# Adafruit_I2C_Quad_Rotary_Encoder_Breakou.net
KiCad netlist of a schematic drawn in EAGLE
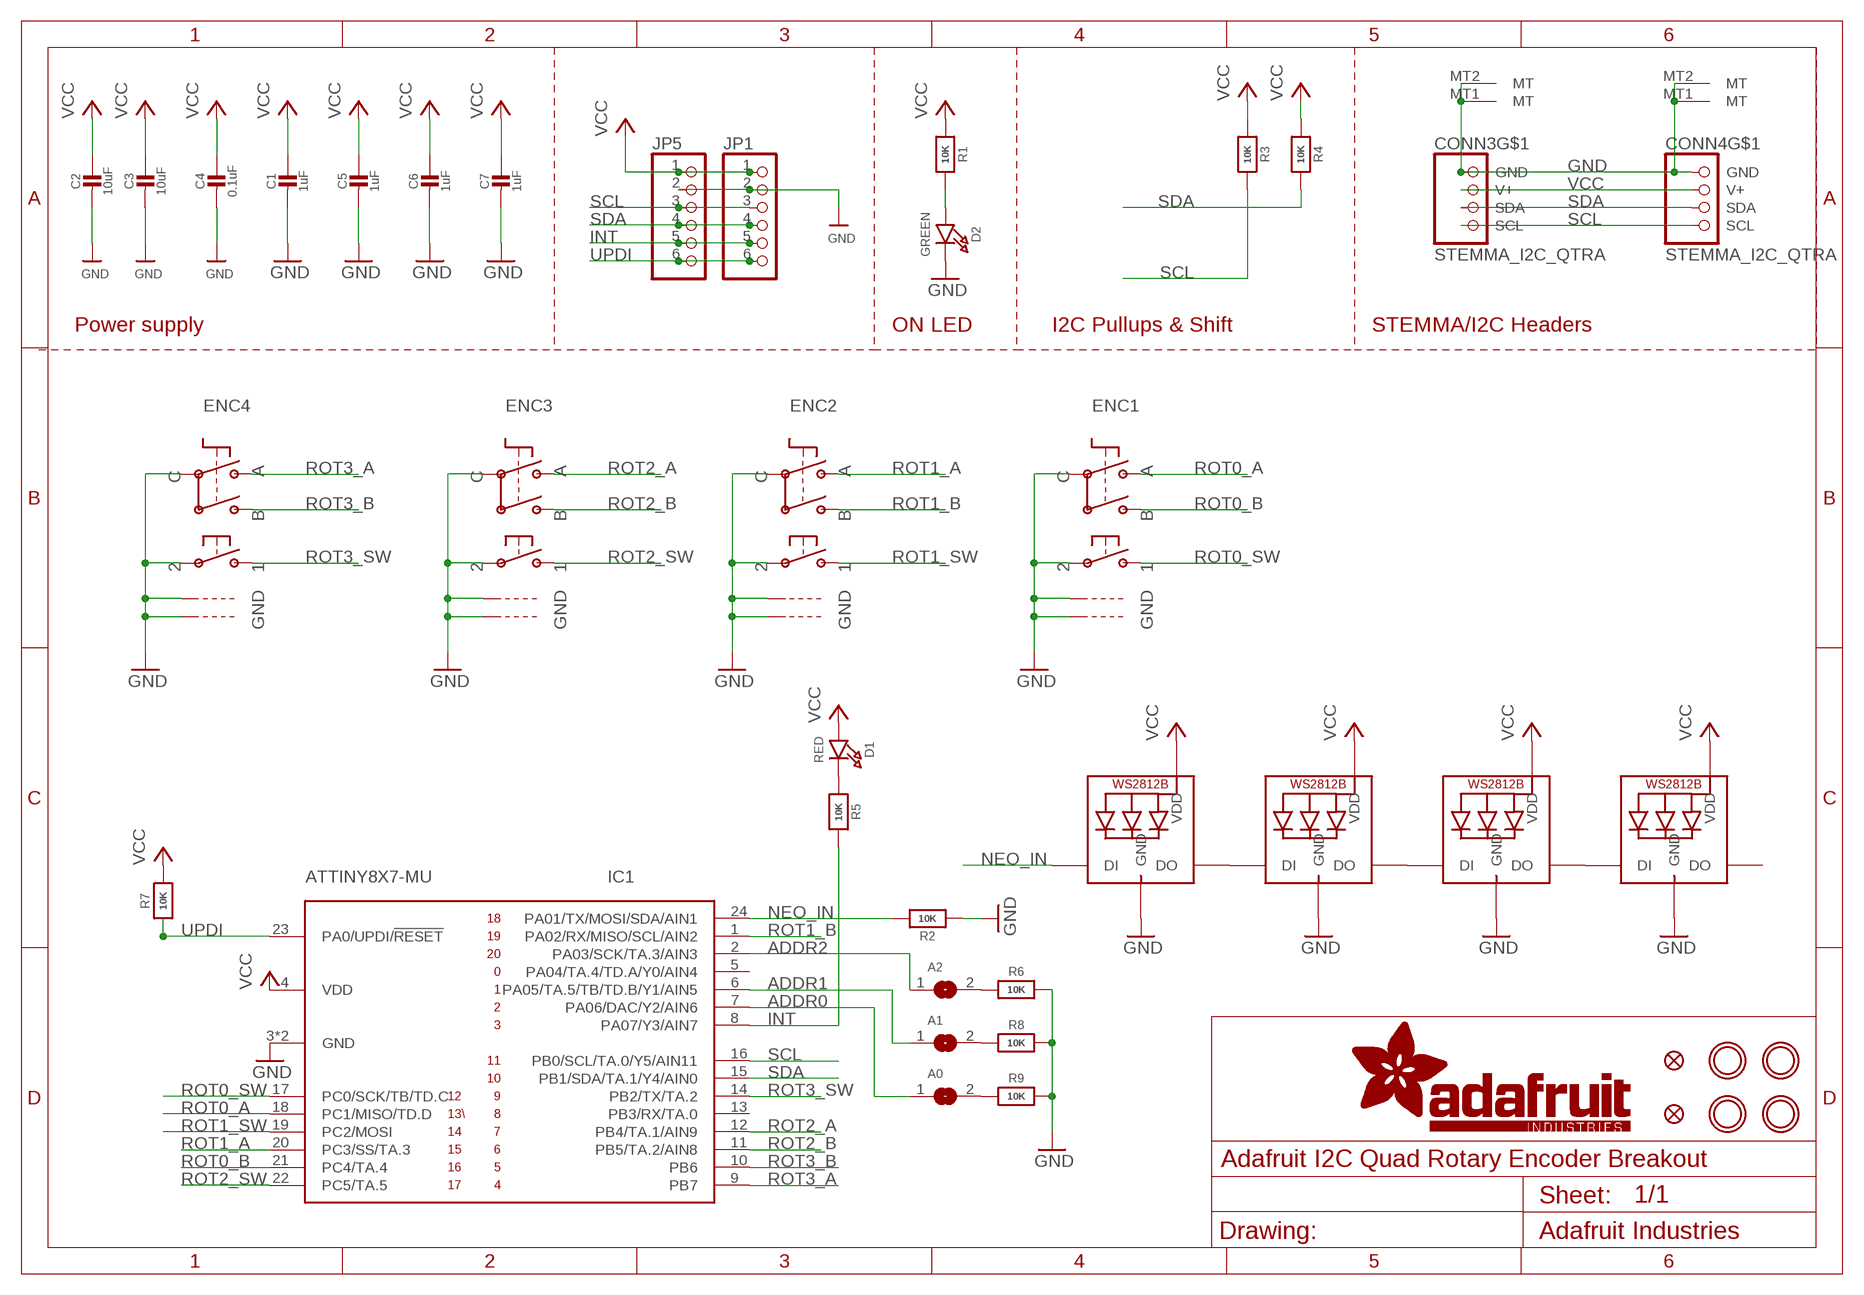
[diagram p0: schematic, sheet 1]

(export (version "E")
  (design (tool "Eeschema 10.0.6"))
  (components
    (comp (ref "A0")
      (value "SOLDERJUMPERCLOSED")
      (footprint "eagle-import:SOLDERJUMPER_CLOSEDWIRE")
      (libsource (lib "eagle-import") (part "SOLDERJUMPERCLOSED"))
    )
    (comp (ref "A1")
      (value "SOLDERJUMPERCLOSED")
      (footprint "eagle-import:SOLDERJUMPER_CLOSEDWIRE")
      (libsource (lib "eagle-import") (part "SOLDERJUMPERCLOSED"))
    )
    (comp (ref "A2")
      (value "SOLDERJUMPERCLOSED")
      (footprint "eagle-import:SOLDERJUMPER_CLOSEDWIRE")
      (libsource (lib "eagle-import") (part "SOLDERJUMPERCLOSED"))
    )
    (comp (ref "C1")
      (value "1uF")
      (footprint "eagle-import:0603-NO")
      (libsource (lib "eagle-import") (part "CAP_CERAMIC0603_NO"))
    )
    (comp (ref "C2")
      (value "10uF")
      (footprint "eagle-import:0805-NO")
      (libsource (lib "eagle-import") (part "CAP_CERAMIC0805-NOOUTLINE"))
    )
    (comp (ref "C3")
      (value "10uF")
      (footprint "eagle-import:0805-NO")
      (libsource (lib "eagle-import") (part "CAP_CERAMIC0805-NOOUTLINE"))
    )
    (comp (ref "C4")
      (value "0.1uF")
      (footprint "eagle-import:0603-NO")
      (libsource (lib "eagle-import") (part "CAP_CERAMIC0603_NO"))
    )
    (comp (ref "C5")
      (value "1uF")
      (footprint "eagle-import:0603-NO")
      (libsource (lib "eagle-import") (part "CAP_CERAMIC0603_NO"))
    )
    (comp (ref "C6")
      (value "1uF")
      (footprint "eagle-import:0603-NO")
      (libsource (lib "eagle-import") (part "CAP_CERAMIC0603_NO"))
    )
    (comp (ref "C7")
      (value "1uF")
      (footprint "eagle-import:0603-NO")
      (libsource (lib "eagle-import") (part "CAP_CERAMIC0603_NO"))
    )
    (comp (ref "CONN3")
      (value "STEMMA_I2C_QTRA")
      (footprint "eagle-import:JST_SH4_RA")
      (libsource (lib "eagle-import") (part "STEMMA_I2C_QTRA"))
    )
    (comp (ref "CONN4")
      (value "STEMMA_I2C_QTRA")
      (footprint "eagle-import:JST_SH4_RA")
      (libsource (lib "eagle-import") (part "STEMMA_I2C_QTRA"))
    )
    (comp (ref "D1")
      (value "RED")
      (footprint "eagle-import:CHIPLED_0603_NOOUTLINE")
      (libsource (lib "eagle-import") (part "LED0603_NOOUTLINE"))
    )
    (comp (ref "D2")
      (value "GREEN")
      (footprint "eagle-import:CHIPLED_0603_NOOUTLINE")
      (libsource (lib "eagle-import") (part "LED0603_NOOUTLINE"))
    )
    (comp (ref "ENC1")
      (value "ENCODER_PLUS_SWITCH_BOURNS_PEC11")
      (footprint "eagle-import:PEC11+SWITCH")
      (libsource (lib "eagle-import") (part "ENCODER_PLUS_SWITCH_PEC11_BOURNS"))
    )
    (comp (ref "ENC2")
      (value "ENCODER_PLUS_SWITCH_BOURNS_PEC11")
      (footprint "eagle-import:PEC11+SWITCH")
      (libsource (lib "eagle-import") (part "ENCODER_PLUS_SWITCH_PEC11_BOURNS"))
    )
    (comp (ref "ENC3")
      (value "ENCODER_PLUS_SWITCH_BOURNS_PEC11")
      (footprint "eagle-import:PEC11+SWITCH")
      (libsource (lib "eagle-import") (part "ENCODER_PLUS_SWITCH_PEC11_BOURNS"))
    )
    (comp (ref "ENC4")
      (value "ENCODER_PLUS_SWITCH_BOURNS_PEC11")
      (footprint "eagle-import:PEC11+SWITCH")
      (libsource (lib "eagle-import") (part "ENCODER_PLUS_SWITCH_PEC11_BOURNS"))
    )
    (comp (ref "FID1")
      (value "FIDUCIAL_1MM")
      (footprint "eagle-import:FIDUCIAL_1MM")
      (libsource (lib "eagle-import") (part "FIDUCIAL_1MM"))
    )
    (comp (ref "FID2")
      (value "FIDUCIAL_1MM")
      (footprint "eagle-import:FIDUCIAL_1MM")
      (libsource (lib "eagle-import") (part "FIDUCIAL_1MM"))
    )
    (comp (ref "IC1")
      (value "ATTINY8X7-MU")
      (footprint "eagle-import:QFN24_4MM")
      (libsource (lib "eagle-import") (part "ATTINY8X7-MU"))
    )
    (comp (ref "JP1")
      (value "HEADER-1X670MIL")
      (footprint "eagle-import:1X06_ROUND_70")
      (libsource (lib "eagle-import") (part "HEADER-1X670MIL"))
    )
    (comp (ref "JP5")
      (value "HEADER-1X670MIL")
      (footprint "eagle-import:1X06_ROUND_70")
      (libsource (lib "eagle-import") (part "HEADER-1X670MIL"))
    )
    (comp (ref "LED1")
      (value "WS2812B_SK6812E")
      (footprint "eagle-import:NEO3535_REVERSE")
      (libsource (lib "eagle-import") (part "WS2812B_SK6812E"))
    )
    (comp (ref "LED2")
      (value "WS2812B_SK6812E")
      (footprint "eagle-import:NEO3535_REVERSE")
      (libsource (lib "eagle-import") (part "WS2812B_SK6812E"))
    )
    (comp (ref "LED3")
      (value "WS2812B_SK6812E")
      (footprint "eagle-import:NEO3535_REVERSE")
      (libsource (lib "eagle-import") (part "WS2812B_SK6812E"))
    )
    (comp (ref "LED4")
      (value "WS2812B_SK6812E")
      (footprint "eagle-import:NEO3535_REVERSE")
      (libsource (lib "eagle-import") (part "WS2812B_SK6812E"))
    )
    (comp (ref "R1")
      (value "10K")
      (footprint "eagle-import:0603-NO")
      (libsource (lib "eagle-import") (part "RESISTOR_0603_NOOUT"))
    )
    (comp (ref "R2")
      (value "10K")
      (footprint "eagle-import:0603-NO")
      (libsource (lib "eagle-import") (part "RESISTOR_0603_NOOUT"))
    )
    (comp (ref "R3")
      (value "10K")
      (footprint "eagle-import:0603-NO")
      (libsource (lib "eagle-import") (part "RESISTOR_0603_NOOUT"))
    )
    (comp (ref "R4")
      (value "10K")
      (footprint "eagle-import:0603-NO")
      (libsource (lib "eagle-import") (part "RESISTOR_0603_NOOUT"))
    )
    (comp (ref "R5")
      (value "10K")
      (footprint "eagle-import:0603-NO")
      (libsource (lib "eagle-import") (part "RESISTOR_0603_NOOUT"))
    )
    (comp (ref "R6")
      (value "10K")
      (footprint "eagle-import:0603-NO")
      (libsource (lib "eagle-import") (part "RESISTOR_0603_NOOUT"))
    )
    (comp (ref "R7")
      (value "10K")
      (footprint "eagle-import:0603-NO")
      (libsource (lib "eagle-import") (part "RESISTOR_0603_NOOUT"))
    )
    (comp (ref "R8")
      (value "10K")
      (footprint "eagle-import:0603-NO")
      (libsource (lib "eagle-import") (part "RESISTOR_0603_NOOUT"))
    )
    (comp (ref "R9")
      (value "10K")
      (footprint "eagle-import:0603-NO")
      (libsource (lib "eagle-import") (part "RESISTOR_0603_NOOUT"))
    )
    (comp (ref "U$3")
      (value "MOUNTINGHOLE2.5")
      (footprint "eagle-import:MOUNTINGHOLE_2.5_PLATED")
      (libsource (lib "eagle-import") (part "MOUNTINGHOLE2.5"))
    )
    (comp (ref "U$17")
      (value "MOUNTINGHOLE2.5")
      (footprint "eagle-import:MOUNTINGHOLE_2.5_PLATED")
      (libsource (lib "eagle-import") (part "MOUNTINGHOLE2.5"))
    )
    (comp (ref "U$19")
      (value "MOUNTINGHOLE2.5")
      (footprint "eagle-import:MOUNTINGHOLE_2.5_PLATED")
      (libsource (lib "eagle-import") (part "MOUNTINGHOLE2.5"))
    )
    (comp (ref "U$21")
      (value "MOUNTINGHOLE2.5")
      (footprint "eagle-import:MOUNTINGHOLE_2.5_PLATED")
      (libsource (lib "eagle-import") (part "MOUNTINGHOLE2.5"))
    )
  )
  (nets
    (net (code "1") (name "/ADDR0") (class "Default")
      (node (ref "A0") (pin "1") (pinfunction "1_1") (pintype "passive"))
      (node (ref "IC1") (pin "7") (pinfunction "PA06/DAC/Y2/AIN6_7") (pintype "bidirectional"))
    )
    (net (code "2") (name "/ADDR1") (class "Default")
      (node (ref "A1") (pin "1") (pinfunction "1_1") (pintype "passive"))
      (node (ref "IC1") (pin "6") (pinfunction "PA05/TA.5/TB/TD.B/Y1/AIN5_6") (pintype "bidirectional"))
    )
    (net (code "3") (name "/ADDR2") (class "Default")
      (node (ref "A2") (pin "1") (pinfunction "1_1") (pintype "passive"))
      (node (ref "IC1") (pin "2") (pinfunction "PA03/SCK/TA.3/AIN3_2") (pintype "bidirectional"))
    )
    (net (code "4") (name "/INT") (class "Default")
      (node (ref "IC1") (pin "8") (pinfunction "PA07/Y3/AIN7_8") (pintype "bidirectional"))
      (node (ref "JP1") (pin "5") (pinfunction "5_5") (pintype "passive"))
      (node (ref "JP5") (pin "5") (pinfunction "5_5") (pintype "passive"))
      (node (ref "R5") (pin "2") (pinfunction "2_2") (pintype "passive"))
    )
    (net (code "5") (name "/NEO_IN") (class "Default")
      (node (ref "IC1") (pin "24") (pinfunction "PA01/TX/MOSI/SDA/AIN1_24") (pintype "bidirectional"))
      (node (ref "LED1") (pin "4-DIN") (pinfunction "DI_4-DIN") (pintype "input"))
      (node (ref "R2") (pin "2") (pinfunction "2_2") (pintype "passive"))
    )
    (net (code "6") (name "/ROT0_A") (class "Default")
      (node (ref "ENC1") (pin "P$A") (pinfunction "P$A_P$A") (pintype "passive"))
      (node (ref "IC1") (pin "18") (pinfunction "PC1/MISO/TD.D_18") (pintype "bidirectional"))
    )
    (net (code "7") (name "/ROT0_B") (class "Default")
      (node (ref "ENC1") (pin "P$B") (pinfunction "P$B_P$B") (pintype "passive"))
      (node (ref "IC1") (pin "21") (pinfunction "PC4/TA.4_21") (pintype "bidirectional"))
    )
    (net (code "8") (name "/ROT0_SW") (class "Default")
      (node (ref "ENC1") (pin "P$1") (pinfunction "P$1_P$1") (pintype "passive"))
      (node (ref "IC1") (pin "17") (pinfunction "PC0/SCK/TB/TD.C_17") (pintype "bidirectional"))
    )
    (net (code "9") (name "/ROT1_A") (class "Default")
      (node (ref "ENC2") (pin "P$A") (pinfunction "P$A_P$A") (pintype "passive"))
      (node (ref "IC1") (pin "20") (pinfunction "PC3/SS/TA.3_20") (pintype "bidirectional"))
    )
    (net (code "10") (name "/ROT1_B") (class "Default")
      (node (ref "ENC2") (pin "P$B") (pinfunction "P$B_P$B") (pintype "passive"))
      (node (ref "IC1") (pin "1") (pinfunction "PA02/RX/MISO/SCL/AIN2_1") (pintype "bidirectional"))
    )
    (net (code "11") (name "/ROT1_SW") (class "Default")
      (node (ref "ENC2") (pin "P$1") (pinfunction "P$1_P$1") (pintype "passive"))
      (node (ref "IC1") (pin "19") (pinfunction "PC2/MOSI_19") (pintype "bidirectional"))
    )
    (net (code "12") (name "/ROT2_A") (class "Default")
      (node (ref "ENC3") (pin "P$A") (pinfunction "P$A_P$A") (pintype "passive"))
      (node (ref "IC1") (pin "12") (pinfunction "PB4/TA.1/AIN9_12") (pintype "bidirectional"))
    )
    (net (code "13") (name "/ROT2_B") (class "Default")
      (node (ref "ENC3") (pin "P$B") (pinfunction "P$B_P$B") (pintype "passive"))
      (node (ref "IC1") (pin "11") (pinfunction "PB5/TA.2/AIN8_11") (pintype "bidirectional"))
    )
    (net (code "14") (name "/ROT2_SW") (class "Default")
      (node (ref "ENC3") (pin "P$1") (pinfunction "P$1_P$1") (pintype "passive"))
      (node (ref "IC1") (pin "22") (pinfunction "PC5/TA.5_22") (pintype "bidirectional"))
    )
    (net (code "15") (name "/ROT3_A") (class "Default")
      (node (ref "ENC4") (pin "P$A") (pinfunction "P$A_P$A") (pintype "passive"))
      (node (ref "IC1") (pin "9") (pinfunction "PB7_9") (pintype "bidirectional"))
    )
    (net (code "16") (name "/ROT3_B") (class "Default")
      (node (ref "ENC4") (pin "P$B") (pinfunction "P$B_P$B") (pintype "passive"))
      (node (ref "IC1") (pin "10") (pinfunction "PB6_10") (pintype "bidirectional"))
    )
    (net (code "17") (name "/ROT3_SW") (class "Default")
      (node (ref "ENC4") (pin "P$1") (pinfunction "P$1_P$1") (pintype "passive"))
      (node (ref "IC1") (pin "14") (pinfunction "PB2/TX/TA.2_14") (pintype "bidirectional"))
    )
    (net (code "18") (name "/SCL") (class "Default")
      (node (ref "CONN3") (pin "4") (pinfunction "SCL_4") (pintype "passive"))
      (node (ref "CONN4") (pin "4") (pinfunction "SCL_4") (pintype "passive"))
      (node (ref "IC1") (pin "16") (pinfunction "PB0/SCL/TA.0/Y5/AIN11_16") (pintype "bidirectional"))
      (node (ref "JP1") (pin "3") (pinfunction "3_3") (pintype "passive"))
      (node (ref "JP5") (pin "3") (pinfunction "3_3") (pintype "passive"))
      (node (ref "R3") (pin "2") (pinfunction "2_2") (pintype "passive"))
    )
    (net (code "19") (name "/SDA") (class "Default")
      (node (ref "CONN3") (pin "3") (pinfunction "SDA_3") (pintype "passive"))
      (node (ref "CONN4") (pin "3") (pinfunction "SDA_3") (pintype "passive"))
      (node (ref "IC1") (pin "15") (pinfunction "PB1/SDA/TA.1/Y4/AIN0_15") (pintype "bidirectional"))
      (node (ref "JP1") (pin "4") (pinfunction "4_4") (pintype "passive"))
      (node (ref "JP5") (pin "4") (pinfunction "4_4") (pintype "passive"))
      (node (ref "R4") (pin "2") (pinfunction "2_2") (pintype "passive"))
    )
    (net (code "20") (name "/UPDI") (class "Default")
      (node (ref "IC1") (pin "23") (pinfunction "PA0/UPDI/~{RESET}_23") (pintype "bidirectional"))
      (node (ref "JP1") (pin "6") (pinfunction "6_6") (pintype "passive"))
      (node (ref "JP5") (pin "6") (pinfunction "6_6") (pintype "passive"))
      (node (ref "R7") (pin "1") (pinfunction "1_1") (pintype "passive"))
    )
    (net (code "21") (name "GND") (class "Default")
      (node (ref "C1") (pin "2") (pinfunction "2_2") (pintype "passive"))
      (node (ref "C2") (pin "2") (pinfunction "2_2") (pintype "passive"))
      (node (ref "C3") (pin "2") (pinfunction "2_2") (pintype "passive"))
      (node (ref "C4") (pin "2") (pinfunction "2_2") (pintype "passive"))
      (node (ref "C5") (pin "2") (pinfunction "2_2") (pintype "passive"))
      (node (ref "C6") (pin "2") (pinfunction "2_2") (pintype "passive"))
      (node (ref "C7") (pin "2") (pinfunction "2_2") (pintype "passive"))
      (node (ref "CONN3") (pin "1") (pinfunction "GND_1") (pintype "passive"))
      (node (ref "CONN3") (pin "MT1") (pinfunction "MT_MT1") (pintype "bidirectional"))
      (node (ref "CONN3") (pin "MT2") (pinfunction "MT_MT2") (pintype "bidirectional"))
      (node (ref "CONN4") (pin "1") (pinfunction "GND_1") (pintype "passive"))
      (node (ref "CONN4") (pin "MT1") (pinfunction "MT_MT1") (pintype "bidirectional"))
      (node (ref "CONN4") (pin "MT2") (pinfunction "MT_MT2") (pintype "bidirectional"))
      (node (ref "D2") (pin "C") (pinfunction "C_C") (pintype "passive"))
      (node (ref "ENC1") (pin "P$2") (pinfunction "P$2_P$2") (pintype "passive"))
      (node (ref "ENC1") (pin "P$C") (pinfunction "P$C_P$C") (pintype "passive"))
      (node (ref "ENC1") (pin "P$GND1") (pinfunction "P$GND1_P$GND1") (pintype "passive"))
      (node (ref "ENC1") (pin "P$GND2") (pinfunction "P$GND2_P$GND2") (pintype "passive"))
      (node (ref "ENC2") (pin "P$2") (pinfunction "P$2_P$2") (pintype "passive"))
      (node (ref "ENC2") (pin "P$C") (pinfunction "P$C_P$C") (pintype "passive"))
      (node (ref "ENC2") (pin "P$GND1") (pinfunction "P$GND1_P$GND1") (pintype "passive"))
      (node (ref "ENC2") (pin "P$GND2") (pinfunction "P$GND2_P$GND2") (pintype "passive"))
      (node (ref "ENC3") (pin "P$2") (pinfunction "P$2_P$2") (pintype "passive"))
      (node (ref "ENC3") (pin "P$C") (pinfunction "P$C_P$C") (pintype "passive"))
      (node (ref "ENC3") (pin "P$GND1") (pinfunction "P$GND1_P$GND1") (pintype "passive"))
      (node (ref "ENC3") (pin "P$GND2") (pinfunction "P$GND2_P$GND2") (pintype "passive"))
      (node (ref "ENC4") (pin "P$2") (pinfunction "P$2_P$2") (pintype "passive"))
      (node (ref "ENC4") (pin "P$C") (pinfunction "P$C_P$C") (pintype "passive"))
      (node (ref "ENC4") (pin "P$GND1") (pinfunction "P$GND1_P$GND1") (pintype "passive"))
      (node (ref "ENC4") (pin "P$GND2") (pinfunction "P$GND2_P$GND2") (pintype "passive"))
      (node (ref "IC1") (pin "3") (pinfunction "GND_3") (pintype "power_in"))
      (node (ref "IC1") (pin "THERM") (pinfunction "GND_THERM") (pintype "power_in"))
      (node (ref "JP1") (pin "2") (pinfunction "2_2") (pintype "passive"))
      (node (ref "JP5") (pin "2") (pinfunction "2_2") (pintype "passive"))
      (node (ref "LED1") (pin "3-GND") (pinfunction "GND_3-GND") (pintype "power_in"))
      (node (ref "LED2") (pin "3-GND") (pinfunction "GND_3-GND") (pintype "power_in"))
      (node (ref "LED3") (pin "3-GND") (pinfunction "GND_3-GND") (pintype "power_in"))
      (node (ref "LED4") (pin "3-GND") (pinfunction "GND_3-GND") (pintype "power_in"))
      (node (ref "R2") (pin "1") (pinfunction "1_1") (pintype "passive"))
      (node (ref "R6") (pin "2") (pinfunction "2_2") (pintype "passive"))
      (node (ref "R8") (pin "2") (pinfunction "2_2") (pintype "passive"))
      (node (ref "R9") (pin "2") (pinfunction "2_2") (pintype "passive"))
    )
    (net (code "22") (name "Net-(A0-Pad2)") (class "Default")
      (node (ref "A0") (pin "2") (pinfunction "2_2") (pintype "passive"))
      (node (ref "R9") (pin "1") (pinfunction "1_1") (pintype "passive"))
    )
    (net (code "23") (name "Net-(A1-Pad2)") (class "Default")
      (node (ref "A1") (pin "2") (pinfunction "2_2") (pintype "passive"))
      (node (ref "R8") (pin "1") (pinfunction "1_1") (pintype "passive"))
    )
    (net (code "24") (name "Net-(A2-Pad2)") (class "Default")
      (node (ref "A2") (pin "2") (pinfunction "2_2") (pintype "passive"))
      (node (ref "R6") (pin "1") (pinfunction "1_1") (pintype "passive"))
    )
    (net (code "25") (name "Net-(D1-PadC)") (class "Default")
      (node (ref "D1") (pin "C") (pinfunction "C_C") (pintype "passive"))
      (node (ref "R5") (pin "1") (pinfunction "1_1") (pintype "passive"))
    )
    (net (code "26") (name "Net-(D2-PadA)") (class "Default")
      (node (ref "D2") (pin "A") (pinfunction "A_A") (pintype "passive"))
      (node (ref "R1") (pin "2") (pinfunction "2_2") (pintype "passive"))
    )
    (net (code "27") (name "Net-(LED1-DO)") (class "Default")
      (node (ref "LED1") (pin "2-DOUT") (pinfunction "DO_2-DOUT") (pintype "output"))
      (node (ref "LED2") (pin "4-DIN") (pinfunction "DI_4-DIN") (pintype "input"))
    )
    (net (code "28") (name "Net-(LED2-DO)") (class "Default")
      (node (ref "LED2") (pin "2-DOUT") (pinfunction "DO_2-DOUT") (pintype "output"))
      (node (ref "LED3") (pin "4-DIN") (pinfunction "DI_4-DIN") (pintype "input"))
    )
    (net (code "29") (name "Net-(LED3-DO)") (class "Default")
      (node (ref "LED3") (pin "2-DOUT") (pinfunction "DO_2-DOUT") (pintype "output"))
      (node (ref "LED4") (pin "4-DIN") (pinfunction "DI_4-DIN") (pintype "input"))
    )
    (net (code "30") (name "VCC") (class "Default")
      (node (ref "C1") (pin "1") (pinfunction "1_1") (pintype "passive"))
      (node (ref "C2") (pin "1") (pinfunction "1_1") (pintype "passive"))
      (node (ref "C3") (pin "1") (pinfunction "1_1") (pintype "passive"))
      (node (ref "C4") (pin "1") (pinfunction "1_1") (pintype "passive"))
      (node (ref "C5") (pin "1") (pinfunction "1_1") (pintype "passive"))
      (node (ref "C6") (pin "1") (pinfunction "1_1") (pintype "passive"))
      (node (ref "C7") (pin "1") (pinfunction "1_1") (pintype "passive"))
      (node (ref "CONN3") (pin "2") (pinfunction "V+_2") (pintype "passive"))
      (node (ref "CONN4") (pin "2") (pinfunction "V+_2") (pintype "passive"))
      (node (ref "D1") (pin "A") (pinfunction "A_A") (pintype "passive"))
      (node (ref "IC1") (pin "4") (pinfunction "VDD_4") (pintype "power_in"))
      (node (ref "JP1") (pin "1") (pinfunction "1_1") (pintype "passive"))
      (node (ref "JP5") (pin "1") (pinfunction "1_1") (pintype "passive"))
      (node (ref "LED1") (pin "1-VDD") (pinfunction "VDD_1-VDD") (pintype "power_in"))
      (node (ref "LED2") (pin "1-VDD") (pinfunction "VDD_1-VDD") (pintype "power_in"))
      (node (ref "LED3") (pin "1-VDD") (pinfunction "VDD_1-VDD") (pintype "power_in"))
      (node (ref "LED4") (pin "1-VDD") (pinfunction "VDD_1-VDD") (pintype "power_in"))
      (node (ref "R1") (pin "1") (pinfunction "1_1") (pintype "passive"))
      (node (ref "R3") (pin "1") (pinfunction "1_1") (pintype "passive"))
      (node (ref "R4") (pin "1") (pinfunction "1_1") (pintype "passive"))
      (node (ref "R7") (pin "2") (pinfunction "2_2") (pintype "passive"))
    )
    (net (code "31") (name "unconnected-(IC1-PA04{slash}TA.4{slash}TD.A{slash}Y0{slash}AIN4-Pad5)") (class "Default")
      (node (ref "IC1") (pin "5") (pinfunction "PA04/TA.4/TD.A/Y0/AIN4_5") (pintype "bidirectional"))
    )
    (net (code "32") (name "unconnected-(IC1-PB3{slash}RX{slash}TA.0-Pad13)") (class "Default")
      (node (ref "IC1") (pin "13") (pinfunction "PB3/RX/TA.0_13") (pintype "bidirectional"))
    )
    (net (code "33") (name "unconnected-(LED4-DO-Pad2-DOUT)") (class "Default")
      (node (ref "LED4") (pin "2-DOUT") (pinfunction "DO_2-DOUT") (pintype "output"))
    )
  )
)
